# projet_pcb_etu_formatA3.net
KiCad netlist of a schematic drawn in Altium Designer
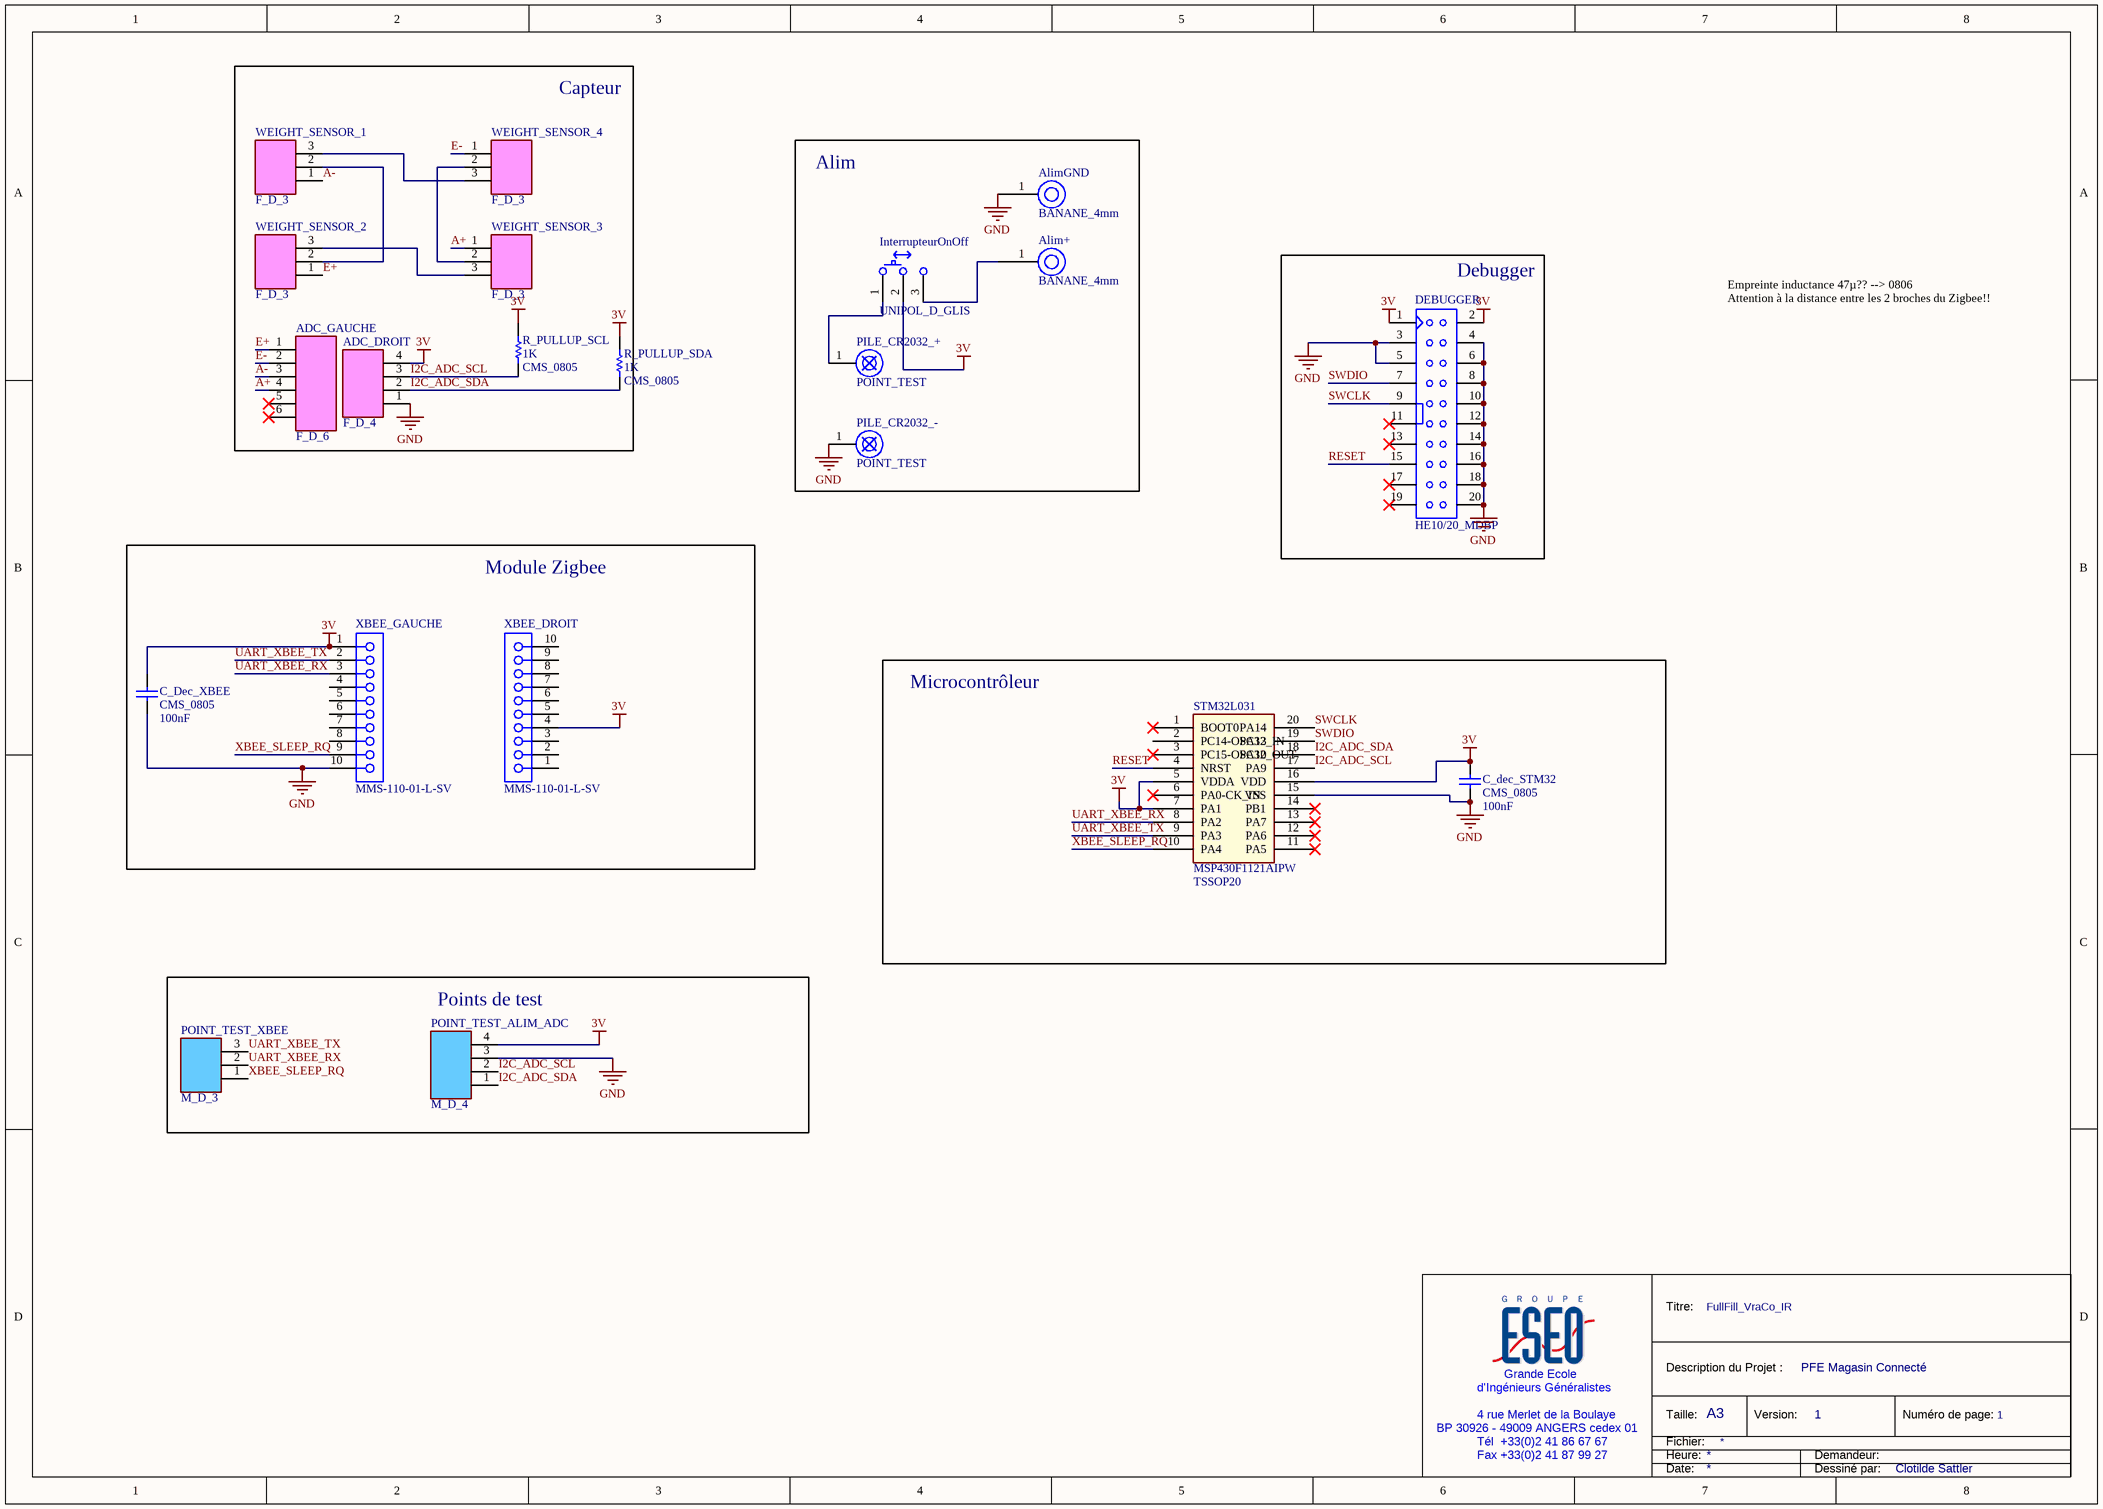
[diagram p0: projet_pcb_etu_formatA3.SchDoc]

(export (version "E")
  (design (tool "Eeschema 10.0.6"))
  (components
    (comp (ref "ADC_DROIT")
      (value "BARRETTE_4 CONTACTS_1 RANGEE_FEMELLE_DROITE")
      (footprint "BARRETTE_4_F_D")
      (description "BARRETTE 4 CONTACTS 1 RANGEE FEMELLE DROITE")
      (fields (field (name "TYPE") "F_D_4"))
      (libsource (lib "connecteurs") (part "BARRETTE_4 CONTACTS_1 RANGEE_FEMELLE_DROITE"))
    )
    (comp (ref "ADC_GAUCHE")
      (value "BARRETTE_6 CONTACTS_1 RANGEE_FEMELLE_DROITE")
      (footprint "BARRETTE_6_F_D")
      (description "BARRETTE 6 CONTACTS 1 RANGEE FEMELLE DROITE")
      (fields (field (name "TYPE") "F_D_6"))
      (libsource (lib "connecteurs") (part "BARRETTE_6 CONTACTS_1 RANGEE_FEMELLE_DROITE"))
    )
    (comp (ref "Alim+")
      (value "DOUILLE BANANE 4mm")
      (footprint "DOUILLE_BANANE_4mm")
      (description "DOUILLE BANANE 4 mm")
      (fields (field (name "TYPE") "BANANE_4mm"))
      (libsource (lib "connecteurs") (part "DOUILLE_BANANE_4mm"))
    )
    (comp (ref "AlimGND")
      (value "DOUILLE BANANE 4mm")
      (footprint "DOUILLE_BANANE_4mm")
      (description "DOUILLE BANANE 4 mm")
      (fields (field (name "TYPE") "BANANE_4mm"))
      (libsource (lib "connecteurs") (part "DOUILLE_BANANE_4mm"))
    )
    (comp (ref "C_dec_STM32")
      (value "100nF")
      (footprint "CONDENSATEUR_CMS_0805")
      (description "CONDENSATEUR CMS CERAMIQUE 0805")
      (fields (field (name "TYPE") "CMS_0805") (field (name "Comment") "CMS_0805"))
      (libsource (lib "composants passifs") (part "CONDENSATEUR_CMS_CER_0805"))
    )
    (comp (ref "C_Dec_XBEE")
      (value "100nF")
      (footprint "CONDENSATEUR_CMS_0805")
      (description "CONDENSATEUR CMS CERAMIQUE 0805")
      (fields (field (name "TYPE") "CMS_0805") (field (name "Comment") "CMS_0805"))
      (libsource (lib "composants passifs") (part "CONDENSATEUR_CMS_CER_0805"))
    )
    (comp (ref "DEBUGGER")
      (value "HE10/20_MALE_DROIT_BAS_PROFIL")
      (footprint "HE10/20_M_D_BP")
      (description "EMBASE HE10/20 MALE DROIT BAS PROFIL")
      (fields (field (name "TYPE") "HE10/20_MDBP"))
      (libsource (lib "connecteurs") (part "HE10/20_MALE_DROIT_BAS_PROFIL"))
    )
    (comp (ref "InterrupteurOnOff")
      (value "INTERRUPTEUR_UNIPOLAIRE_DROIT_GLISSIERE")
      (footprint "INTER_UNIPOL_DROIT_GLISS")
      (description "INTERRUPTEUR UNIPOLAIRE DROIT A GLISSIERE")
      (fields (field (name "TYPE") "UNIPOL_D_GLIS"))
      (libsource (lib "commutation") (part "INTERRUPTEUR_UNIPOLAIRE_DROIT_GLISSIERE"))
    )
    (comp (ref "PILE_CR2032_+")
      (value "POINT_TEST")
      (footprint "POINT_TEST")
      (description "POINT TEST")
      (libsource (lib "connecteurs") (part "POINT_TEST"))
    )
    (comp (ref "PILE_CR2032_-")
      (value "POINT_TEST")
      (footprint "POINT_TEST")
      (description "POINT TEST")
      (libsource (lib "connecteurs") (part "POINT_TEST"))
    )
    (comp (ref "POINT_TEST_ALIM_ADC")
      (value "BARRETTE_4 CONTACTS_1 RANGEE_MALE_DROITE")
      (footprint "BARRETTE_4_M_D")
      (description "BARRETTE 4 CONTACTS 1 RANGEE MALE DROITE")
      (fields (field (name "TYPE") "M_D_4"))
      (libsource (lib "connecteurs") (part "BARRETTE_4 CONTACTS_1 RANGEE_MALE_DROITE"))
    )
    (comp (ref "POINT_TEST_XBEE")
      (value "BARRETTE 3 CONTACTS 1 RANGEE MALE DROITE")
      (footprint "BARRETTE_3_M_D")
      (fields (field (name "TYPE") "M_D_3"))
      (libsource (lib "connecteurs") (part "BARRETTE_3 CONTACTS_1 RANGEE_MALE_DROITE"))
    )
    (comp (ref "R_PULLUP_SCL")
      (value "1K")
      (footprint "RESISTANCE_CMS_0805")
      (description "RESISTANCE CMS 0805")
      (fields (field (name "TYPE") "CMS_0805") (field (name "Comment") "RESISTANCE_CMS_0805"))
      (libsource (lib "composants passifs") (part "RESISTANCE_CMS_0805"))
    )
    (comp (ref "R_PULLUP_SDA")
      (value "1K")
      (footprint "RESISTANCE_CMS_0805")
      (description "RESISTANCE CMS 0805")
      (fields (field (name "TYPE") "CMS_0805") (field (name "Comment") "RESISTANCE_CMS_0805"))
      (libsource (lib "composants passifs") (part "RESISTANCE_CMS_0805"))
    )
    (comp (ref "STM32L031")
      (value "MSP430F1121AIPW_TSSOP20")
      (footprint "TSSOP20_PAS=0.65_LARG=6.4_LONG=6.5")
      (description "MICROCONTROLEUR FLASH - 16BITS - TSSOP20")
      (fields (field (name "TYPE") "MSP430F1121AIPW") (field (name "PACKAGE") "TSSOP20"))
      (libsource (lib "circuits integres") (part "MSP430F1121AIPW_TSSOP20"))
    )
    (comp (ref "WEIGHT_SENSOR_1")
      (value "BARRETTE 3 CONTACTS 1 RANGEE FEMELLE DROITE")
      (footprint "BARRETTE_3_F_D")
      (fields (field (name "TYPE") "F_D_3"))
      (libsource (lib "") (part "BARRETTE_3 CONTACTS_1 RANGEE_FEMELLE_DROITE_1"))
    )
    (comp (ref "WEIGHT_SENSOR_2")
      (value "BARRETTE 3 CONTACTS 1 RANGEE FEMELLE DROITE")
      (footprint "BARRETTE_3_F_D")
      (fields (field (name "TYPE") "F_D_3"))
      (libsource (lib "") (part "BARRETTE_3 CONTACTS_1 RANGEE_FEMELLE_DROITE_1"))
    )
    (comp (ref "WEIGHT_SENSOR_3")
      (value "BARRETTE 3 CONTACTS 1 RANGEE FEMELLE DROITE")
      (footprint "BARRETTE_3_F_D")
      (fields (field (name "TYPE") "F_D_3"))
      (libsource (lib "connecteurs") (part "BARRETTE_3 CONTACTS_1 RANGEE_FEMELLE_DROITE"))
    )
    (comp (ref "WEIGHT_SENSOR_4")
      (value "BARRETTE 3 CONTACTS 1 RANGEE FEMELLE DROITE")
      (footprint "BARRETTE_3_F_D")
      (fields (field (name "TYPE") "F_D_3"))
      (libsource (lib "connecteurs") (part "BARRETTE_3 CONTACTS_1 RANGEE_FEMELLE_DROITE"))
    )
    (comp (ref "XBEE_DROIT")
      (value "MMS-110-01-L-SV")
      (footprint "SMTC-MMS-110-01-X-SV")
      (fields (field (name "MANUFACTURER") "Samtec"))
      (libsource (lib "Samtec_2_mm_Pitch_Socket_Strips") (part "MMS-110-01-L-SV"))
    )
    (comp (ref "XBEE_GAUCHE")
      (value "MMS-110-01-L-SV")
      (footprint "SMTC-MMS-110-01-X-SV")
      (fields (field (name "MANUFACTURER") "Samtec"))
      (libsource (lib "Samtec_2_mm_Pitch_Socket_Strips") (part "MMS-110-01-L-SV"))
    )
  )
  (nets
    (net (code "1") (name "/A+") (class "Default")
      (node (ref "ADC_GAUCHE") (pin "4") (pinfunction "4_4") (pintype "passive"))
      (node (ref "WEIGHT_SENSOR_3") (pin "1") (pinfunction "1_1") (pintype "passive"))
    )
    (net (code "2") (name "/A-") (class "Default")
      (node (ref "ADC_GAUCHE") (pin "3") (pinfunction "3_3") (pintype "passive"))
      (node (ref "WEIGHT_SENSOR_1") (pin "1") (pinfunction "1_1") (pintype "passive"))
    )
    (net (code "3") (name "/E+") (class "Default")
      (node (ref "ADC_GAUCHE") (pin "1") (pinfunction "1_1") (pintype "passive"))
      (node (ref "WEIGHT_SENSOR_2") (pin "1") (pinfunction "1_1") (pintype "passive"))
    )
    (net (code "4") (name "/E-") (class "Default")
      (node (ref "ADC_GAUCHE") (pin "2") (pinfunction "2_2") (pintype "passive"))
      (node (ref "WEIGHT_SENSOR_4") (pin "1") (pinfunction "1_1") (pintype "passive"))
    )
    (net (code "5") (name "/I2C_ADC_SCL") (class "Default")
      (node (ref "ADC_DROIT") (pin "3") (pinfunction "3_3") (pintype "passive"))
      (node (ref "POINT_TEST_ALIM_ADC") (pin "2") (pinfunction "2_2") (pintype "passive"))
      (node (ref "R_PULLUP_SCL") (pin "1") (pinfunction "1_1") (pintype "passive"))
      (node (ref "STM32L031") (pin "17") (pinfunction "PA9_17") (pintype "passive"))
    )
    (net (code "6") (name "/I2C_ADC_SDA") (class "Default")
      (node (ref "ADC_DROIT") (pin "2") (pinfunction "2_2") (pintype "passive"))
      (node (ref "POINT_TEST_ALIM_ADC") (pin "1") (pinfunction "1_1") (pintype "passive"))
      (node (ref "R_PULLUP_SDA") (pin "1") (pinfunction "1_1") (pintype "passive"))
      (node (ref "STM32L031") (pin "18") (pinfunction "PA10_18") (pintype "passive"))
    )
    (net (code "7") (name "/RESET") (class "Default")
      (node (ref "DEBUGGER") (pin "15") (pinfunction "15_15") (pintype "passive"))
      (node (ref "STM32L031") (pin "4") (pinfunction "NRST_4") (pintype "passive"))
    )
    (net (code "8") (name "/SWCLK") (class "Default")
      (node (ref "DEBUGGER") (pin "9") (pinfunction "9_9") (pintype "passive"))
      (node (ref "STM32L031") (pin "20") (pinfunction "PA14_20") (pintype "passive"))
    )
    (net (code "9") (name "/SWDIO") (class "Default")
      (node (ref "DEBUGGER") (pin "7") (pinfunction "7_7") (pintype "passive"))
      (node (ref "STM32L031") (pin "19") (pinfunction "PA13_19") (pintype "passive"))
    )
    (net (code "10") (name "/UART_XBEE_RX") (class "Default")
      (node (ref "POINT_TEST_XBEE") (pin "2") (pinfunction "2_2") (pintype "passive"))
      (node (ref "STM32L031") (pin "8") (pinfunction "PA2_8") (pintype "passive"))
      (node (ref "XBEE_GAUCHE") (pin "3") (pinfunction "3_3") (pintype "passive"))
    )
    (net (code "11") (name "/UART_XBEE_TX") (class "Default")
      (node (ref "POINT_TEST_XBEE") (pin "3") (pinfunction "3_3") (pintype "passive"))
      (node (ref "STM32L031") (pin "9") (pinfunction "PA3_9") (pintype "passive"))
      (node (ref "XBEE_GAUCHE") (pin "2") (pinfunction "2_2") (pintype "passive"))
    )
    (net (code "12") (name "/XBEE_SLEEP_RQ") (class "Default")
      (node (ref "POINT_TEST_XBEE") (pin "1") (pinfunction "1_1") (pintype "passive"))
      (node (ref "STM32L031") (pin "10") (pinfunction "PA4_10") (pintype "passive"))
      (node (ref "XBEE_GAUCHE") (pin "9") (pinfunction "9_9") (pintype "passive"))
    )
    (net (code "13") (name "3V") (class "Default")
      (node (ref "ADC_DROIT") (pin "4") (pinfunction "4_4") (pintype "passive"))
      (node (ref "C_Dec_XBEE") (pin "2") (pinfunction "2_2") (pintype "passive"))
      (node (ref "C_dec_STM32") (pin "2") (pinfunction "2_2") (pintype "passive"))
      (node (ref "DEBUGGER") (pin "1") (pinfunction "1_1") (pintype "passive"))
      (node (ref "DEBUGGER") (pin "2") (pinfunction "2_2") (pintype "passive"))
      (node (ref "InterrupteurOnOff") (pin "2") (pinfunction "2_2") (pintype "passive"))
      (node (ref "POINT_TEST_ALIM_ADC") (pin "4") (pinfunction "4_4") (pintype "passive"))
      (node (ref "R_PULLUP_SCL") (pin "2") (pinfunction "2_2") (pintype "passive"))
      (node (ref "R_PULLUP_SDA") (pin "2") (pinfunction "2_2") (pintype "passive"))
      (node (ref "STM32L031") (pin "16") (pinfunction "VDD_16") (pintype "passive"))
      (node (ref "STM32L031") (pin "5") (pinfunction "VDDA_5") (pintype "passive"))
      (node (ref "STM32L031") (pin "7") (pinfunction "PA1_7") (pintype "passive"))
      (node (ref "XBEE_DROIT") (pin "4") (pinfunction "4_4") (pintype "passive"))
      (node (ref "XBEE_GAUCHE") (pin "1") (pinfunction "1_1") (pintype "passive"))
    )
    (net (code "14") (name "GND") (class "Default")
      (node (ref "ADC_DROIT") (pin "1") (pinfunction "1_1") (pintype "passive"))
      (node (ref "AlimGND") (pin "1") (pinfunction "1_1") (pintype "passive"))
      (node (ref "C_Dec_XBEE") (pin "1") (pinfunction "1_1") (pintype "passive"))
      (node (ref "C_dec_STM32") (pin "1") (pinfunction "1_1") (pintype "passive"))
      (node (ref "DEBUGGER") (pin "10") (pinfunction "10_10") (pintype "passive"))
      (node (ref "DEBUGGER") (pin "12") (pinfunction "12_12") (pintype "passive"))
      (node (ref "DEBUGGER") (pin "14") (pinfunction "14_14") (pintype "passive"))
      (node (ref "DEBUGGER") (pin "16") (pinfunction "16_16") (pintype "passive"))
      (node (ref "DEBUGGER") (pin "18") (pinfunction "18_18") (pintype "passive"))
      (node (ref "DEBUGGER") (pin "20") (pinfunction "20_20") (pintype "passive"))
      (node (ref "DEBUGGER") (pin "3") (pinfunction "3_3") (pintype "passive"))
      (node (ref "DEBUGGER") (pin "4") (pinfunction "4_4") (pintype "passive"))
      (node (ref "DEBUGGER") (pin "5") (pinfunction "5_5") (pintype "passive"))
      (node (ref "DEBUGGER") (pin "6") (pinfunction "6_6") (pintype "passive"))
      (node (ref "DEBUGGER") (pin "8") (pinfunction "8_8") (pintype "passive"))
      (node (ref "PILE_CR2032_-") (pin "1") (pinfunction "3_1") (pintype "passive"))
      (node (ref "POINT_TEST_ALIM_ADC") (pin "3") (pinfunction "3_3") (pintype "passive"))
      (node (ref "STM32L031") (pin "15") (pinfunction "VSS_15") (pintype "passive"))
      (node (ref "XBEE_GAUCHE") (pin "10") (pinfunction "10_10") (pintype "passive"))
    )
    (net (code "15") (name "Net-(Alim+-Pad1)") (class "Default")
      (node (ref "Alim+") (pin "1") (pinfunction "1_1") (pintype "passive"))
      (node (ref "InterrupteurOnOff") (pin "3") (pinfunction "3_3") (pintype "passive"))
    )
    (net (code "16") (name "Net-(PILE_CR2032_+-3)") (class "Default")
      (node (ref "InterrupteurOnOff") (pin "1") (pinfunction "1_1") (pintype "passive"))
      (node (ref "PILE_CR2032_+") (pin "1") (pinfunction "3_1") (pintype "passive"))
    )
    (net (code "17") (name "Net-(WEIGHT_SENSOR_1-Pad2)") (class "Default")
      (node (ref "WEIGHT_SENSOR_1") (pin "2") (pinfunction "2_2") (pintype "passive"))
      (node (ref "WEIGHT_SENSOR_2") (pin "2") (pinfunction "2_2") (pintype "passive"))
    )
    (net (code "18") (name "Net-(WEIGHT_SENSOR_1-Pad3)") (class "Default")
      (node (ref "WEIGHT_SENSOR_1") (pin "3") (pinfunction "3_3") (pintype "passive"))
      (node (ref "WEIGHT_SENSOR_4") (pin "3") (pinfunction "3_3") (pintype "passive"))
    )
    (net (code "19") (name "Net-(WEIGHT_SENSOR_2-Pad3)") (class "Default")
      (node (ref "WEIGHT_SENSOR_2") (pin "3") (pinfunction "3_3") (pintype "passive"))
      (node (ref "WEIGHT_SENSOR_3") (pin "3") (pinfunction "3_3") (pintype "passive"))
    )
    (net (code "20") (name "Net-(WEIGHT_SENSOR_3-Pad2)") (class "Default")
      (node (ref "WEIGHT_SENSOR_3") (pin "2") (pinfunction "2_2") (pintype "passive"))
      (node (ref "WEIGHT_SENSOR_4") (pin "2") (pinfunction "2_2") (pintype "passive"))
    )
    (net (code "21") (name "unconnected-(ADC_GAUCHE-Pad5)") (class "Default")
      (node (ref "ADC_GAUCHE") (pin "5") (pinfunction "5_5") (pintype "passive+no_connect"))
    )
    (net (code "22") (name "unconnected-(ADC_GAUCHE-Pad6)") (class "Default")
      (node (ref "ADC_GAUCHE") (pin "6") (pinfunction "6_6") (pintype "passive+no_connect"))
    )
    (net (code "23") (name "unconnected-(DEBUGGER-Pad11)") (class "Default")
      (node (ref "DEBUGGER") (pin "11") (pinfunction "11_11") (pintype "passive+no_connect"))
    )
    (net (code "24") (name "unconnected-(DEBUGGER-Pad13)") (class "Default")
      (node (ref "DEBUGGER") (pin "13") (pinfunction "13_13") (pintype "passive+no_connect"))
    )
    (net (code "25") (name "unconnected-(DEBUGGER-Pad17)") (class "Default")
      (node (ref "DEBUGGER") (pin "17") (pinfunction "17_17") (pintype "passive+no_connect"))
    )
    (net (code "26") (name "unconnected-(DEBUGGER-Pad19)") (class "Default")
      (node (ref "DEBUGGER") (pin "19") (pinfunction "19_19") (pintype "passive+no_connect"))
    )
    (net (code "27") (name "unconnected-(STM32L031-BOOT0-Pad1)") (class "Default")
      (node (ref "STM32L031") (pin "1") (pinfunction "BOOT0_1") (pintype "passive+no_connect"))
    )
    (net (code "28") (name "unconnected-(STM32L031-PA0-CK_IN-Pad6)") (class "Default")
      (node (ref "STM32L031") (pin "6") (pinfunction "PA0-CK_IN_6") (pintype "passive+no_connect"))
    )
    (net (code "29") (name "unconnected-(STM32L031-PA5-Pad11)") (class "Default")
      (node (ref "STM32L031") (pin "11") (pinfunction "PA5_11") (pintype "passive+no_connect"))
    )
    (net (code "30") (name "unconnected-(STM32L031-PA6-Pad12)") (class "Default")
      (node (ref "STM32L031") (pin "12") (pinfunction "PA6_12") (pintype "passive+no_connect"))
    )
    (net (code "31") (name "unconnected-(STM32L031-PA7-Pad13)") (class "Default")
      (node (ref "STM32L031") (pin "13") (pinfunction "PA7_13") (pintype "passive+no_connect"))
    )
    (net (code "32") (name "unconnected-(STM32L031-PB1-Pad14)") (class "Default")
      (node (ref "STM32L031") (pin "14") (pinfunction "PB1_14") (pintype "passive+no_connect"))
    )
    (net (code "33") (name "unconnected-(STM32L031-PC14-OSC32_IN-Pad2)") (class "Default")
      (node (ref "STM32L031") (pin "2") (pinfunction "PC14-OSC32_IN_2") (pintype "passive"))
    )
    (net (code "34") (name "unconnected-(STM32L031-PC15-OSC32_OUT-Pad3)") (class "Default")
      (node (ref "STM32L031") (pin "3") (pinfunction "PC15-OSC32_OUT_3") (pintype "passive+no_connect"))
    )
    (net (code "35") (name "unconnected-(XBEE_DROIT-Pad1)") (class "Default")
      (node (ref "XBEE_DROIT") (pin "1") (pinfunction "1_1") (pintype "passive"))
    )
    (net (code "36") (name "unconnected-(XBEE_DROIT-Pad2)") (class "Default")
      (node (ref "XBEE_DROIT") (pin "2") (pinfunction "2_2") (pintype "passive"))
    )
    (net (code "37") (name "unconnected-(XBEE_DROIT-Pad3)") (class "Default")
      (node (ref "XBEE_DROIT") (pin "3") (pinfunction "3_3") (pintype "passive"))
    )
    (net (code "38") (name "unconnected-(XBEE_DROIT-Pad5)") (class "Default")
      (node (ref "XBEE_DROIT") (pin "5") (pinfunction "5_5") (pintype "passive"))
    )
    (net (code "39") (name "unconnected-(XBEE_DROIT-Pad6)") (class "Default")
      (node (ref "XBEE_DROIT") (pin "6") (pinfunction "6_6") (pintype "passive"))
    )
    (net (code "40") (name "unconnected-(XBEE_DROIT-Pad7)") (class "Default")
      (node (ref "XBEE_DROIT") (pin "7") (pinfunction "7_7") (pintype "passive"))
    )
    (net (code "41") (name "unconnected-(XBEE_DROIT-Pad8)") (class "Default")
      (node (ref "XBEE_DROIT") (pin "8") (pinfunction "8_8") (pintype "passive"))
    )
    (net (code "42") (name "unconnected-(XBEE_DROIT-Pad9)") (class "Default")
      (node (ref "XBEE_DROIT") (pin "9") (pinfunction "9_9") (pintype "passive"))
    )
    (net (code "43") (name "unconnected-(XBEE_DROIT-Pad10)") (class "Default")
      (node (ref "XBEE_DROIT") (pin "10") (pinfunction "10_10") (pintype "passive"))
    )
    (net (code "44") (name "unconnected-(XBEE_GAUCHE-Pad4)") (class "Default")
      (node (ref "XBEE_GAUCHE") (pin "4") (pinfunction "4_4") (pintype "passive"))
    )
    (net (code "45") (name "unconnected-(XBEE_GAUCHE-Pad5)") (class "Default")
      (node (ref "XBEE_GAUCHE") (pin "5") (pinfunction "5_5") (pintype "passive"))
    )
    (net (code "46") (name "unconnected-(XBEE_GAUCHE-Pad6)") (class "Default")
      (node (ref "XBEE_GAUCHE") (pin "6") (pinfunction "6_6") (pintype "passive"))
    )
    (net (code "47") (name "unconnected-(XBEE_GAUCHE-Pad7)") (class "Default")
      (node (ref "XBEE_GAUCHE") (pin "7") (pinfunction "7_7") (pintype "passive"))
    )
    (net (code "48") (name "unconnected-(XBEE_GAUCHE-Pad8)") (class "Default")
      (node (ref "XBEE_GAUCHE") (pin "8") (pinfunction "8_8") (pintype "passive"))
    )
  )
)
